# EXT_LED.net
KiCad netlist of a schematic drawn in Altium Designer
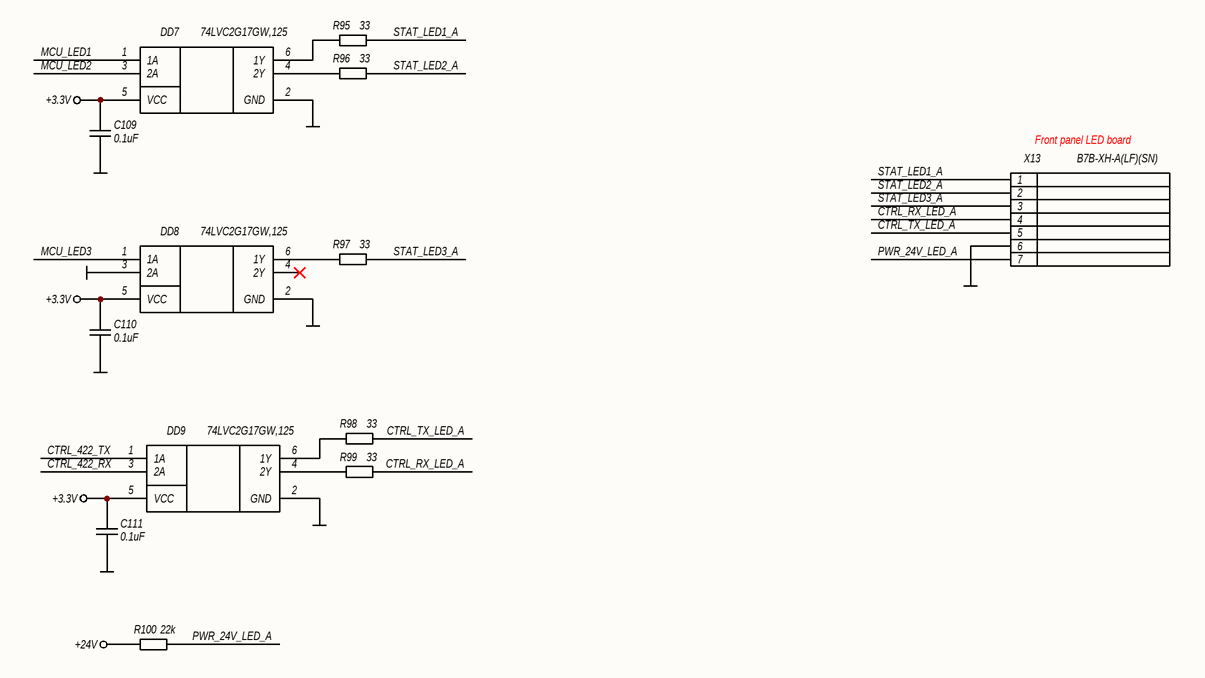
[diagram p0: EXT_LED.SchDoc]

(export (version "E")
  (design (tool "Eeschema 10.0.6"))
  (components
    (comp (ref "C109")
      (value "0.1uF")
      (footprint "C0603N")
      (description "Конденсатор")
      (libsource (lib "Components Library") (part "CAP_FIXED"))
    )
    (comp (ref "C110")
      (value "0.1uF")
      (footprint "C0603N")
      (description "Конденсатор")
      (libsource (lib "Components Library") (part "CAP_FIXED"))
    )
    (comp (ref "C111")
      (value "0.1uF")
      (footprint "C0603N")
      (description "Конденсатор")
      (libsource (lib "Components Library") (part "CAP_FIXED"))
    )
    (comp (ref "DD7")
      (value "74LVC2G17GW,125")
      (footprint "SOT363-2")
      (description "Микросхема сдвоенный триггер Шмитта")
      (libsource (lib "Components Library") (part "74LVC2G17"))
    )
    (comp (ref "DD8")
      (value "74LVC2G17GW,125")
      (footprint "SOT363-2")
      (description "Микросхема сдвоенный триггер Шмитта")
      (libsource (lib "Components Library") (part "74LVC2G17"))
    )
    (comp (ref "DD9")
      (value "74LVC2G17GW,125")
      (footprint "SOT363-2")
      (description "Микросхема сдвоенный триггер Шмитта")
      (libsource (lib "Components Library") (part "74LVC2G17"))
    )
    (comp (ref "R95")
      (value "33")
      (footprint "R0603N")
      (description "Резистор")
      (libsource (lib "Components Library") (part "RES_FIXED"))
    )
    (comp (ref "R96")
      (value "33")
      (footprint "R0603N")
      (description "Резистор")
      (libsource (lib "Components Library") (part "RES_FIXED"))
    )
    (comp (ref "R97")
      (value "33")
      (footprint "R0603N")
      (description "Резистор")
      (libsource (lib "Components Library") (part "RES_FIXED"))
    )
    (comp (ref "R98")
      (value "33")
      (footprint "R0603N")
      (description "Резистор")
      (libsource (lib "Components Library") (part "RES_FIXED"))
    )
    (comp (ref "R99")
      (value "33")
      (footprint "R0603N")
      (description "Резистор")
      (libsource (lib "Components Library") (part "RES_FIXED"))
    )
    (comp (ref "R100")
      (value "22k")
      (footprint "R0603N")
      (description "Резистор")
      (libsource (lib "") (part "RES_FIXED_1"))
    )
    (comp (ref "X13")
      (value "B7B-XH-A(LF)(SN)")
      (footprint "B7B-XH-A")
      (description "Разъем, 7 контактов")
      (libsource (lib "Components Library") (part "Connector 7"))
    )
  )
  (nets
    (net (code "1") (name "+3.3V") (class "Default")
      (node (ref "C109") (pin "2") (pinfunction "2_2") (pintype "passive"))
      (node (ref "C110") (pin "2") (pinfunction "2_2") (pintype "passive"))
      (node (ref "C111") (pin "2") (pinfunction "2_2") (pintype "passive"))
      (node (ref "DD7") (pin "5") (pinfunction "VCC_5") (pintype "power_in"))
      (node (ref "DD8") (pin "5") (pinfunction "VCC_5") (pintype "power_in"))
      (node (ref "DD9") (pin "5") (pinfunction "VCC_5") (pintype "power_in"))
    )
    (net (code "2") (name "+24V") (class "Default")
      (node (ref "R100") (pin "2") (pinfunction "2_2") (pintype "passive"))
    )
    (net (code "3") (name "/CTRL_422_RX") (class "Default")
      (node (ref "DD9") (pin "3") (pinfunction "2A_3") (pintype "power_in"))
    )
    (net (code "4") (name "/CTRL_422_TX") (class "Default")
      (node (ref "DD9") (pin "1") (pinfunction "1A_1") (pintype "power_in"))
    )
    (net (code "5") (name "/CTRL_RX_LED_A") (class "Default")
      (node (ref "R99") (pin "2") (pinfunction "2_2") (pintype "passive"))
      (node (ref "X13") (pin "4") (pinfunction "4_4") (pintype "power_in"))
    )
    (net (code "6") (name "/CTRL_TX_LED_A") (class "Default")
      (node (ref "R98") (pin "2") (pinfunction "2_2") (pintype "passive"))
      (node (ref "X13") (pin "5") (pinfunction "5_5") (pintype "power_in"))
    )
    (net (code "7") (name "/MCU_LED1") (class "Default")
      (node (ref "DD7") (pin "1") (pinfunction "1A_1") (pintype "power_in"))
    )
    (net (code "8") (name "/MCU_LED2") (class "Default")
      (node (ref "DD7") (pin "3") (pinfunction "2A_3") (pintype "power_in"))
    )
    (net (code "9") (name "/MCU_LED3") (class "Default")
      (node (ref "DD8") (pin "1") (pinfunction "1A_1") (pintype "power_in"))
    )
    (net (code "10") (name "/PWR_24V_LED_A") (class "Default")
      (node (ref "R100") (pin "1") (pinfunction "1_1") (pintype "passive"))
      (node (ref "X13") (pin "7") (pinfunction "7_7") (pintype "power_in"))
    )
    (net (code "11") (name "/STAT_LED1_A") (class "Default")
      (node (ref "R95") (pin "2") (pinfunction "2_2") (pintype "passive"))
      (node (ref "X13") (pin "1") (pinfunction "1_1") (pintype "power_in"))
    )
    (net (code "12") (name "/STAT_LED2_A") (class "Default")
      (node (ref "R96") (pin "2") (pinfunction "2_2") (pintype "passive"))
      (node (ref "X13") (pin "2") (pinfunction "2_2") (pintype "power_in"))
    )
    (net (code "13") (name "/STAT_LED3_A") (class "Default")
      (node (ref "R97") (pin "2") (pinfunction "2_2") (pintype "passive"))
      (node (ref "X13") (pin "3") (pinfunction "3_3") (pintype "power_in"))
    )
    (net (code "14") (name "GND") (class "Default")
      (node (ref "C109") (pin "1") (pinfunction "1_1") (pintype "passive"))
      (node (ref "C110") (pin "1") (pinfunction "1_1") (pintype "passive"))
      (node (ref "C111") (pin "1") (pinfunction "1_1") (pintype "passive"))
      (node (ref "DD7") (pin "2") (pinfunction "GND_2") (pintype "power_in"))
      (node (ref "DD8") (pin "2") (pinfunction "GND_2") (pintype "power_in"))
      (node (ref "DD8") (pin "3") (pinfunction "2A_3") (pintype "power_in"))
      (node (ref "DD9") (pin "2") (pinfunction "GND_2") (pintype "power_in"))
      (node (ref "X13") (pin "6") (pinfunction "6_6") (pintype "power_in"))
    )
    (net (code "15") (name "Net-(DD7-1Y)") (class "Default")
      (node (ref "DD7") (pin "6") (pinfunction "1Y_6") (pintype "power_in"))
      (node (ref "R95") (pin "1") (pinfunction "1_1") (pintype "passive"))
    )
    (net (code "16") (name "Net-(DD7-2Y)") (class "Default")
      (node (ref "DD7") (pin "4") (pinfunction "2Y_4") (pintype "power_in"))
      (node (ref "R96") (pin "1") (pinfunction "1_1") (pintype "passive"))
    )
    (net (code "17") (name "Net-(DD8-1Y)") (class "Default")
      (node (ref "DD8") (pin "6") (pinfunction "1Y_6") (pintype "power_in"))
      (node (ref "R97") (pin "1") (pinfunction "1_1") (pintype "passive"))
    )
    (net (code "18") (name "Net-(DD9-1Y)") (class "Default")
      (node (ref "DD9") (pin "6") (pinfunction "1Y_6") (pintype "power_in"))
      (node (ref "R98") (pin "1") (pinfunction "1_1") (pintype "passive"))
    )
    (net (code "19") (name "Net-(DD9-2Y)") (class "Default")
      (node (ref "DD9") (pin "4") (pinfunction "2Y_4") (pintype "power_in"))
      (node (ref "R99") (pin "1") (pinfunction "1_1") (pintype "passive"))
    )
    (net (code "20") (name "unconnected-(DD8-2Y-Pad4)") (class "Default")
      (node (ref "DD8") (pin "4") (pinfunction "2Y_4") (pintype "power_in+no_connect"))
    )
  )
)
